# Power.net
KiCad netlist of a schematic drawn in Altium Designer
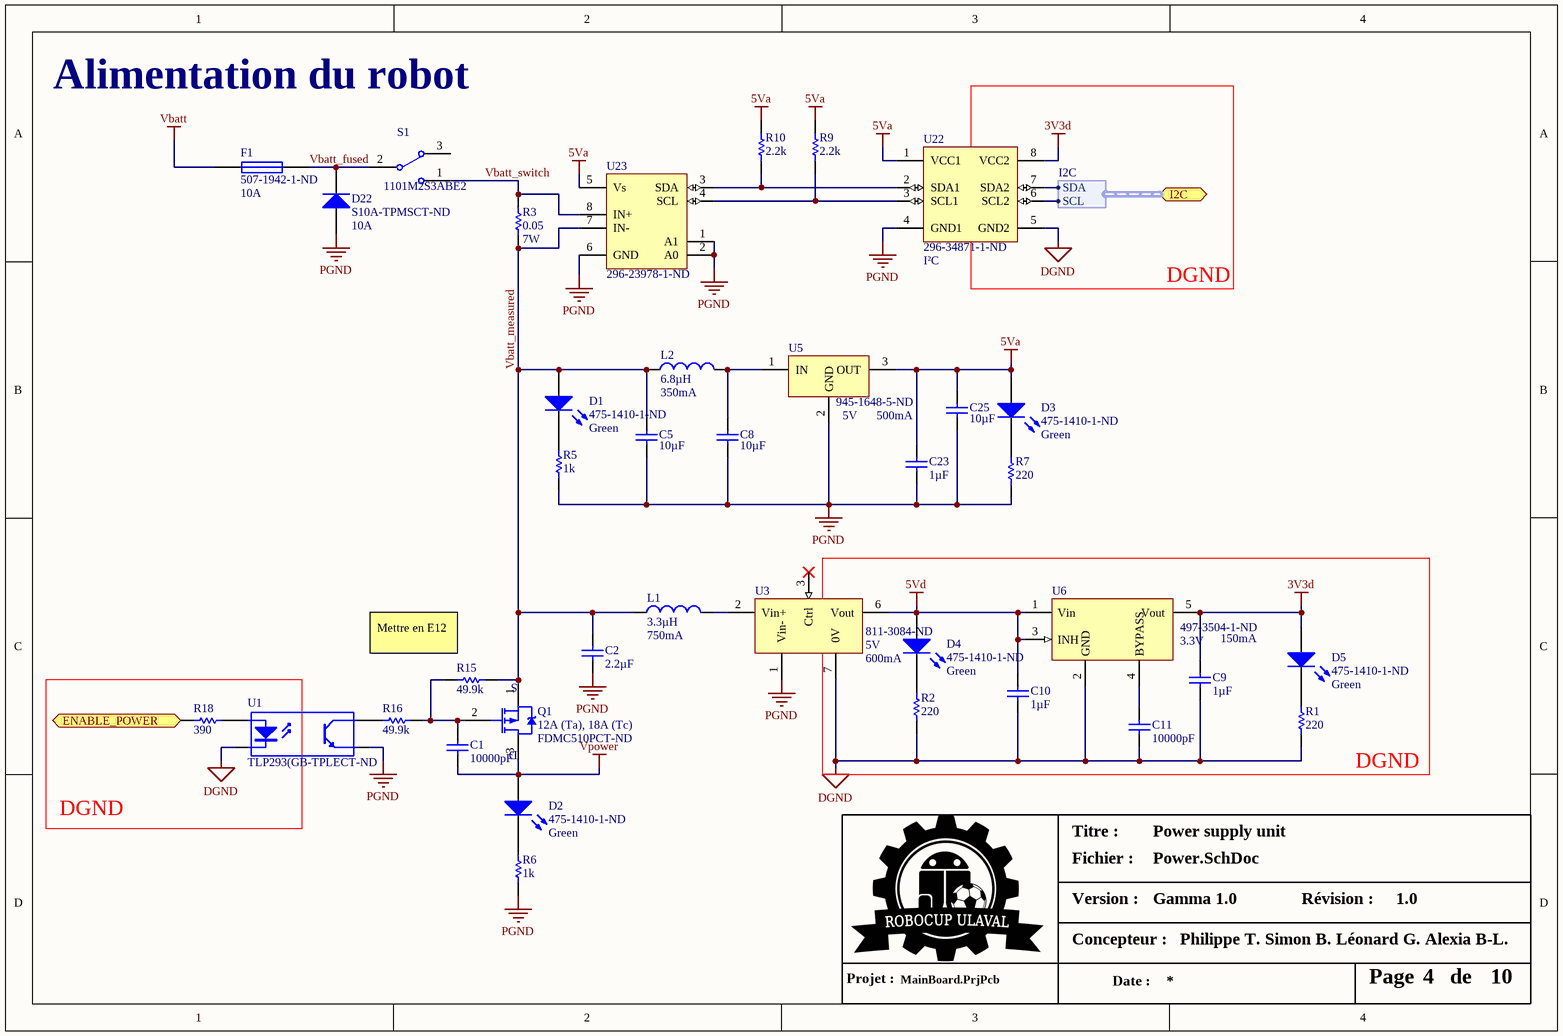
[diagram p0: Power.SchDoc]

(export (version "E")
  (design (tool "Eeschema 10.0.6"))
  (components
    (comp (ref "C1")
      (value "GRM188R71H103KA01D")
      (footprint "0603")
      (description "CAP CER 10000PF 50V X7R 0603")
      (fields
        (field (name "MANUFACTURER") "Murata Electronics North America")
        (field (name "TOLERANCE") "±10%")
        (field (name "CAPACITANCE") "10000pF")
      )
      (libsource (lib "ResCap") (part "GRM188R71H103KA01D"))
    )
    (comp (ref "C2")
      (value "CL21B225KAFNNWE")
      (footprint "0805")
      (description "CAP CER 2.2UF 25V X7R 0805")
      (fields
        (field (name "MANUFACTURER") "Samsung Electro-Mechanics America, Inc.")
        (field (name "TOLERANCE") "±10%")
        (field (name "CAPACITANCE") "2.2µF")
      )
      (libsource (lib "ResCap") (part "CL21B225KAFNNWE"))
    )
    (comp (ref "C5")
      (value "GMK316AB7106KL-TR")
      (footprint "1206")
      (description "CAP CER 10UF 35V X7R 1206")
      (fields
        (field (name "MANUFACTURER") "Taiyo Yuden")
        (field (name "CAPACITANCE") "10µF")
        (field (name "TOLERANCE") "±10%")
      )
      (libsource (lib "ResCap") (part "GMK316AB7106KL-TR"))
    )
    (comp (ref "C8")
      (value "GMK316AB7106KL-TR")
      (footprint "1206")
      (description "CAP CER 10UF 35V X7R 1206")
      (fields
        (field (name "MANUFACTURER") "Taiyo Yuden")
        (field (name "CAPACITANCE") "10µF")
        (field (name "TOLERANCE") "±10%")
      )
      (libsource (lib "ResCap") (part "GMK316AB7106KL-TR"))
    )
    (comp (ref "C9")
      (value "CL21B105KBFNFNE")
      (footprint "0805")
      (description "CAP CER 1UF 50V X7R 0805")
      (fields
        (field (name "MANUFACTURER") "Samsung Electro-Mechanics America, Inc.")
        (field (name "TOLERANCE") "±10%")
        (field (name "CAPACITANCE") "1µF")
      )
      (libsource (lib "ResCap") (part "CL21B105KBFNFNE"))
    )
    (comp (ref "C10")
      (value "CL21B105KBFNFNE")
      (footprint "0805")
      (description "CAP CER 1UF 50V X7R 0805")
      (fields
        (field (name "MANUFACTURER") "Samsung Electro-Mechanics America, Inc.")
        (field (name "TOLERANCE") "±10%")
        (field (name "CAPACITANCE") "1µF")
      )
      (libsource (lib "ResCap") (part "CL21B105KBFNFNE"))
    )
    (comp (ref "C11")
      (value "GRM188R71H103KA01D")
      (footprint "0603")
      (description "CAP CER 10000PF 50V X7R 0603")
      (fields
        (field (name "MANUFACTURER") "Murata Electronics North America")
        (field (name "TOLERANCE") "±10%")
        (field (name "CAPACITANCE") "10000pF")
      )
      (libsource (lib "ResCap") (part "GRM188R71H103KA01D"))
    )
    (comp (ref "C23")
      (value "CL21B105KBFNFNE")
      (footprint "0805")
      (description "CAP CER 1UF 50V X7R 0805")
      (fields
        (field (name "MANUFACTURER") "Samsung Electro-Mechanics America, Inc.")
        (field (name "TOLERANCE") "±10%")
        (field (name "CAPACITANCE") "1µF")
      )
      (libsource (lib "ResCap") (part "CL21B105KBFNFNE"))
    )
    (comp (ref "C25")
      (value "GMK316AB7106KL-TR")
      (footprint "1206")
      (description "CAP CER 10UF 35V X7R 1206")
      (fields
        (field (name "MANUFACTURER") "Taiyo Yuden")
        (field (name "CAPACITANCE") "10µF")
        (field (name "TOLERANCE") "±10%")
      )
      (libsource (lib "ResCap") (part "GMK316AB7106KL-TR"))
    )
    (comp (ref "D1")
      (value "LG R971-KN-1")
      (footprint "0805")
      (description "LED GREEN DIFFUSED 0805 SMD")
      (fields
        (field (name "MANUFACTURER") "OSRAM Opto Semiconductors Inc.")
        (field (name "SUPPLIER PART NUMBER 1") "475-1410-1-ND")
        (field (name "COLOR") "Green")
      )
      (libsource (lib "MainBoard") (part "LG R971-KN-1"))
    )
    (comp (ref "D2")
      (value "LG R971-KN-1")
      (footprint "0805")
      (description "LED GREEN DIFFUSED 0805 SMD")
      (fields
        (field (name "MANUFACTURER") "OSRAM Opto Semiconductors Inc.")
        (field (name "SUPPLIER PART NUMBER 1") "475-1410-1-ND")
        (field (name "COLOR") "Green")
      )
      (libsource (lib "MainBoard") (part "LG R971-KN-1"))
    )
    (comp (ref "D3")
      (value "LG R971-KN-1")
      (footprint "0805")
      (description "LED GREEN DIFFUSED 0805 SMD")
      (fields
        (field (name "MANUFACTURER") "OSRAM Opto Semiconductors Inc.")
        (field (name "SUPPLIER PART NUMBER 1") "475-1410-1-ND")
        (field (name "COLOR") "Green")
      )
      (libsource (lib "MainBoard") (part "LG R971-KN-1"))
    )
    (comp (ref "D4")
      (value "LG R971-KN-1")
      (footprint "0805")
      (description "LED GREEN DIFFUSED 0805 SMD")
      (fields
        (field (name "MANUFACTURER") "OSRAM Opto Semiconductors Inc.")
        (field (name "SUPPLIER PART NUMBER 1") "475-1410-1-ND")
        (field (name "COLOR") "Green")
      )
      (libsource (lib "MainBoard") (part "LG R971-KN-1"))
    )
    (comp (ref "D5")
      (value "LG R971-KN-1")
      (footprint "0805")
      (description "LED GREEN DIFFUSED 0805 SMD")
      (fields
        (field (name "MANUFACTURER") "OSRAM Opto Semiconductors Inc.")
        (field (name "SUPPLIER PART NUMBER 1") "475-1410-1-ND")
        (field (name "COLOR") "Green")
      )
      (libsource (lib "MainBoard") (part "LG R971-KN-1"))
    )
    (comp (ref "D22")
      (value "S10A-TP")
      (footprint "SMC")
      (description "DIODE GEN PURP 50V 10A DO214AB")
      (fields
        (field (name "MANUFACTURER") "Micro Commercial Co")
        (field (name "SUPPLIER PART NUMBER 1") "S10A-TPMSCT-ND")
        (field (name "CURRENT - AVERAGE RECTIFIED (IO)") "10A")
      )
      (libsource (lib "MainBoard") (part "S10A-TP"))
    )
    (comp (ref "F1")
      (value "C1H 10")
      (footprint "1206")
      (description "FUSE BOARD MNT 10A 125VAC 32VDC")
      (fields
        (field (name "MANUFACTURER") "Bel Fuse Inc.")
        (field (name "SUPPLIER PART NUMBER 1") "507-1942-1-ND")
        (field (name "CURRENT RATING") "10A")
      )
      (libsource (lib "MainBoard") (part "C1H 10"))
    )
    (comp (ref "L1")
      (value "MLZ2012N3R3LT000")
      (footprint "0805")
      (description "FIXED IND 3.3UH 750MA 150 MOHM")
      (fields
        (field (name "MANUFACTURER") "TDK Corporation")
        (field (name "TOLERANCE") "±20%")
        (field (name "INDUCTANCE") "3.3µH")
        (field (name "CURRENT RATING") "750mA")
      )
      (libsource (lib "MainBoard") (part "MLZ2012N3R3LT000"))
    )
    (comp (ref "L2")
      (value "MLZ2012M6R8WT000")
      (footprint "0805")
      (description "FIXED IND 6.8UH 350MA 400 MOHM")
      (fields
        (field (name "MANUFACTURER") "TDK Corporation")
        (field (name "TOLERANCE") "±20%")
        (field (name "INDUCTANCE") "6.8µH")
        (field (name "CURRENT RATING") "350mA")
      )
      (libsource (lib "MainBoard") (part "MLZ2012M6R8WT000"))
    )
    (comp (ref "Q1")
      (value "FDMC510P")
      (footprint "PowerPAK 1212-8")
      (description "MOSFET P-CH 20V 18A 8-MLP")
      (fields
        (field (name "MANUFACTURER") "Fairchild Semiconductor")
        (field (name "CURRENT - CONTINUOUS DRAIN (ID) @ 25°C") "12A (Ta), 18A (Tc)")
        (field (name "SUPPLIER PART NUMBER 1") "FDMC510PCT-ND")
      )
      (libsource (lib "MainBoard") (part "FDMC510P"))
    )
    (comp (ref "R1")
      (value "RC1206JR-07220RL")
      (footprint "1206")
      (description "RES SMD 220 OHM 5% 1/4W 1206")
      (fields
        (field (name "MANUFACTURER") "Yageo")
        (field (name "TOLERANCE") "±5%")
        (field (name "RESISTANCE (OHMS)") "220")
      )
      (libsource (lib "ResCap") (part "RC1206JR-07220RL"))
    )
    (comp (ref "R2")
      (value "RC1206JR-07220RL")
      (footprint "1206")
      (description "RES SMD 220 OHM 5% 1/4W 1206")
      (fields
        (field (name "MANUFACTURER") "Yageo")
        (field (name "TOLERANCE") "±5%")
        (field (name "RESISTANCE (OHMS)") "220")
      )
      (libsource (lib "ResCap") (part "RC1206JR-07220RL"))
    )
    (comp (ref "R3")
      (value "WSHM2818R0500FEA")
      (footprint "RESC7146X15N")
      (description "RES SMD 0.05 OHM 1% 7W 2818")
      (fields
        (field (name "MANUFACTURER") "Vishay Dale")
        (field (name "TOLERANCE") "±1%")
        (field (name "RESISTANCE (OHMS)") "0.05")
        (field (name "POWER (WATTS)") "7W")
      )
      (libsource (lib "ResCap") (part "WSHM2818R0500FEA"))
    )
    (comp (ref "R5")
      (value "RNCP1206FTD1K00")
      (footprint "1206")
      (description "RES SMD 1K OHM 1% 1/2W 1206")
      (fields
        (field (name "MANUFACTURER") "Stackpole Electronics Inc.")
        (field (name "TOLERANCE") "±1%")
        (field (name "RESISTANCE (OHMS)") "1k")
      )
      (libsource (lib "ResCap") (part "RNCP1206FTD1K00"))
    )
    (comp (ref "R6")
      (value "RC0603FR-072K2L")
      (footprint "1206")
      (description "RES SMD 1K OHM 1% 1/2W 1206")
      (fields
        (field (name "MANUFACTURER") "Stackpole Electronics Inc.")
        (field (name "MANUFACTURER PART NUMBER") "RNCP1206FTD1K00")
        (field (name "RESISTANCE (OHMS)") "1k")
      )
      (libsource (lib "ResCap") (part "RNCP1206FTD1K00"))
    )
    (comp (ref "R7")
      (value "RC1206JR-07220RL")
      (footprint "1206")
      (description "RES SMD 220 OHM 5% 1/4W 1206")
      (fields
        (field (name "MANUFACTURER") "Yageo")
        (field (name "TOLERANCE") "±5%")
        (field (name "RESISTANCE (OHMS)") "220")
      )
      (libsource (lib "ResCap") (part "RC1206JR-07220RL"))
    )
    (comp (ref "R9")
      (value "RC0603FR-072K2L")
      (footprint "0603")
      (description "RES SMD 2.2K OHM 1% 1/10W 0603")
      (fields
        (field (name "MANUFACTURER") "Yageo")
        (field (name "TOLERANCE") "±1%")
        (field (name "RESISTANCE (OHMS)") "2.2k")
      )
      (libsource (lib "ResCap") (part "RC0603FR-072K2L"))
    )
    (comp (ref "R10")
      (value "RC0603FR-072K2L")
      (footprint "0603")
      (description "RES SMD 2.2K OHM 1% 1/10W 0603")
      (fields
        (field (name "MANUFACTURER") "Yageo")
        (field (name "TOLERANCE") "±1%")
        (field (name "RESISTANCE (OHMS)") "2.2k")
      )
      (libsource (lib "ResCap") (part "RC0603FR-072K2L"))
    )
    (comp (ref "R15")
      (value "RC0603FR-0749K9L")
      (footprint "0603")
      (description "RES SMD 49.9K OHM 1% 1/10W 0603")
      (fields
        (field (name "MANUFACTURER") "Yageo")
        (field (name "TOLERANCE") "±1%")
        (field (name "RESISTANCE (OHMS)") "49.9k")
      )
      (libsource (lib "ResCap") (part "RC0603FR-0749K9L"))
    )
    (comp (ref "R16")
      (value "RC0603FR-0749K9L")
      (footprint "0603")
      (description "RES SMD 49.9K OHM 1% 1/10W 0603")
      (fields
        (field (name "MANUFACTURER") "Yageo")
        (field (name "TOLERANCE") "±1%")
        (field (name "RESISTANCE (OHMS)") "49.9k")
      )
      (libsource (lib "ResCap") (part "RC0603FR-0749K9L"))
    )
    (comp (ref "R18")
      (value "RC0603JR-07390RL")
      (footprint "0603")
      (description "RES SMD 390 OHM 5% 1/10W 0603")
      (fields
        (field (name "MANUFACTURER") "Yageo")
        (field (name "TOLERANCE") "±5%")
        (field (name "RESISTANCE (OHMS)") "390")
      )
      (libsource (lib "ResCap") (part "RC0603JR-07390RL"))
    )
    (comp (ref "S1")
      (value "1101M2S3ABE2")
      (footprint "C&K Switch")
      (description "SWITCH SLIDE SPDT 0.4VA 20V")
      (fields (field (name "MANUFACTURER") "C&K Components"))
      (libsource (lib "MainBoard") (part "1101M2S3ABE2"))
    )
    (comp (ref "U1")
      (value "TLP293(GB-TPL,E")
      (footprint "SOIC127P700X220-4N")
      (description "OPTOISOLATOR 3.75KV TRANS 4-SO")
      (fields
        (field (name "MANUFACTURER") "Toshiba Semiconductor and Storage")
        (field (name "SUPPLIER PART NUMBER 1") "TLP293(GB-TPLECT-ND")
      )
      (libsource (lib "MainBoard") (part "TLP293(GB-TPL,E"))
    )
    (comp (ref "U3")
      (value "NCS3S1205SC")
      (footprint "NCS3S")
      (description "DC/DC CONVERTER 5V 3W")
      (fields
        (field (name "MANUFACTURER") "Murata Power Solutions Inc.")
        (field (name "SUPPLIER PART NUMBER 1") "811-3084-ND")
        (field (name "VOLTAGE - OUTPUT 1") "5V")
        (field (name "CURRENT - OUTPUT (MAX)") "600mA")
      )
      (libsource (lib "MainBoard") (part "NCS3S1205SC"))
    )
    (comp (ref "U5")
      (value "R-78E5.0-0.5")
      (footprint "3-SIP MOdule")
      (description "CONV DC/DC 5V 500MA OUT THRU")
      (fields
        (field (name "MANUFACTURER") "Recom Power")
        (field (name "SUPPLIER PART NUMBER 1") "945-1648-5-ND")
        (field (name "VOLTAGE - OUTPUT 1") "5V")
        (field (name "CURRENT - OUTPUT (MAX)") "500mA")
      )
      (libsource (lib "MainBoard") (part "R-78E5.0-0.5"))
    )
    (comp (ref "U6")
      (value "LD3985M33R")
      (footprint "SOT-23-5")
      (description "IC REG LDO 3.3V 0.15A SOT23-5")
      (fields
        (field (name "MANUFACTURER") "STMicroelectronics")
        (field (name "SUPPLIER PART NUMBER 1") "497-3504-1-ND")
        (field (name "VOLTAGE - OUTPUT") "3.3V")
        (field (name "CURRENT - OUTPUT") "150mA")
      )
      (libsource (lib "MainBoard") (part "LD3985M33R"))
    )
    (comp (ref "U22")
      (value "ISO1540DR")
      (footprint "SOIC127P600X175-8N")
      (description "DGTL ISO 2.5KV 2CH I2C 8SOIC")
      (fields
        (field (name "MANUFACTURER") "Texas Instruments")
        (field (name "SUPPLIER PART NUMBER 1") "296-34871-1-ND")
        (field (name "TYPE") "I²C")
      )
      (libsource (lib "MainBoard") (part "ISO1540DR"))
    )
    (comp (ref "U23")
      (value "INA219AIDR")
      (footprint "SOIC127P600X175-8N")
      (description "IC CURRENT MONITOR 1% 8SOIC")
      (fields
        (field (name "MANUFACTURER") "Texas Instruments")
        (field (name "SUPPLIER PART NUMBER 1") "296-23978-1-ND")
      )
      (libsource (lib "MainBoard") (part "INA219AIDR"))
    )
  )
  (nets
    (net (code "2") (name "/ENABLE_POWER") (class "Default")
      (node (ref "R18") (pin "1") (pinfunction "1_1") (pintype "passive"))
    )
    (net (code "3") (name "/SCL") (class "Default")
      (node (ref "U22") (pin "6") (pinfunction "SCL2_6") (pintype "bidirectional"))
    )
    (net (code "4") (name "/SDA") (class "Default")
      (node (ref "U22") (pin "7") (pinfunction "SDA2_7") (pintype "bidirectional"))
    )
    (net (code "5") (name "/Vbatt_fused") (class "Default")
      (node (ref "D22") (pin "2") (pinfunction "K_2") (pintype "passive"))
      (node (ref "F1") (pin "2") (pinfunction "2_2") (pintype "passive"))
      (node (ref "S1") (pin "2") (pinfunction "2_2") (pintype "passive"))
    )
    (net (code "6") (name "/Vbatt_measured") (class "Default")
      (node (ref "C2") (pin "2") (pinfunction "2_2") (pintype "passive"))
      (node (ref "C5") (pin "2") (pinfunction "2_2") (pintype "passive"))
      (node (ref "D1") (pin "1") (pinfunction "A_1") (pintype "passive"))
      (node (ref "L1") (pin "1") (pinfunction "1_1") (pintype "passive"))
      (node (ref "L2") (pin "1") (pinfunction "1_1") (pintype "passive"))
      (node (ref "Q1") (pin "1") (pinfunction "S_1") (pintype "passive"))
      (node (ref "R15") (pin "2") (pinfunction "2_2") (pintype "passive"))
      (node (ref "R3") (pin "1") (pinfunction "1_1") (pintype "passive"))
      (node (ref "U23") (pin "7") (pinfunction "IN-_7") (pintype "power_in"))
    )
    (net (code "7") (name "/Vbatt_switch") (class "Default")
      (node (ref "R3") (pin "2") (pinfunction "2_2") (pintype "passive"))
      (node (ref "S1") (pin "1") (pinfunction "1_1") (pintype "passive"))
      (node (ref "U23") (pin "8") (pinfunction "IN+_8") (pintype "power_in"))
    )
    (net (code "9") (name "3V3d") (class "Default")
      (node (ref "C9") (pin "2") (pinfunction "2_2") (pintype "passive"))
      (node (ref "D5") (pin "1") (pinfunction "A_1") (pintype "passive"))
      (node (ref "U22") (pin "8") (pinfunction "VCC2_8") (pintype "power_in"))
      (node (ref "U6") (pin "5") (pinfunction "Vout_5") (pintype "power_in"))
    )
    (net (code "10") (name "5Va") (class "Default")
      (node (ref "C23") (pin "2") (pinfunction "2_2") (pintype "passive"))
      (node (ref "C25") (pin "2") (pinfunction "2_2") (pintype "passive"))
      (node (ref "D3") (pin "1") (pinfunction "A_1") (pintype "passive"))
      (node (ref "R10") (pin "2") (pinfunction "2_2") (pintype "passive"))
      (node (ref "R9") (pin "2") (pinfunction "2_2") (pintype "passive"))
      (node (ref "U22") (pin "1") (pinfunction "VCC1_1") (pintype "power_in"))
      (node (ref "U23") (pin "5") (pinfunction "Vs_5") (pintype "power_in"))
      (node (ref "U5") (pin "3") (pinfunction "OUT_3") (pintype "power_in"))
    )
    (net (code "11") (name "5Vd") (class "Default")
      (node (ref "C10") (pin "2") (pinfunction "2_2") (pintype "passive"))
      (node (ref "D4") (pin "1") (pinfunction "A_1") (pintype "passive"))
      (node (ref "U3") (pin "6") (pinfunction "Vout_6") (pintype "power_in"))
      (node (ref "U6") (pin "1") (pinfunction "Vin_1") (pintype "power_in"))
      (node (ref "U6") (pin "3") (pinfunction "INH_3") (pintype "input"))
    )
    (net (code "12") (name "DGND") (class "Default")
      (node (ref "C10") (pin "1") (pinfunction "1_1") (pintype "passive"))
      (node (ref "C11") (pin "1") (pinfunction "1_1") (pintype "passive"))
      (node (ref "C9") (pin "1") (pinfunction "1_1") (pintype "passive"))
      (node (ref "R1") (pin "1") (pinfunction "1_1") (pintype "passive"))
      (node (ref "R2") (pin "1") (pinfunction "1_1") (pintype "passive"))
      (node (ref "U1") (pin "2") (pinfunction "K_2") (pintype "passive"))
      (node (ref "U22") (pin "5") (pinfunction "GND2_5") (pintype "power_in"))
      (node (ref "U3") (pin "7") (pinfunction "0V_7") (pintype "power_in"))
      (node (ref "U6") (pin "2") (pinfunction "GND_2") (pintype "power_in"))
    )
    (net (code "13") (name "Net-(D1-K)") (class "Default")
      (node (ref "D1") (pin "2") (pinfunction "K_2") (pintype "passive"))
      (node (ref "R5") (pin "2") (pinfunction "2_2") (pintype "passive"))
    )
    (net (code "14") (name "Net-(D2-K)") (class "Default")
      (node (ref "D2") (pin "2") (pinfunction "K_2") (pintype "passive"))
      (node (ref "R6") (pin "2") (pinfunction "2_2") (pintype "passive"))
    )
    (net (code "15") (name "Net-(D3-K)") (class "Default")
      (node (ref "D3") (pin "2") (pinfunction "K_2") (pintype "passive"))
      (node (ref "R7") (pin "2") (pinfunction "2_2") (pintype "passive"))
    )
    (net (code "16") (name "Net-(D4-K)") (class "Default")
      (node (ref "D4") (pin "2") (pinfunction "K_2") (pintype "passive"))
      (node (ref "R2") (pin "2") (pinfunction "2_2") (pintype "passive"))
    )
    (net (code "17") (name "Net-(D5-K)") (class "Default")
      (node (ref "D5") (pin "2") (pinfunction "K_2") (pintype "passive"))
      (node (ref "R1") (pin "2") (pinfunction "2_2") (pintype "passive"))
    )
    (net (code "18") (name "Net-(Q1-G)") (class "Default")
      (node (ref "C1") (pin "2") (pinfunction "2_2") (pintype "passive"))
      (node (ref "Q1") (pin "2") (pinfunction "G_2") (pintype "passive"))
      (node (ref "R15") (pin "1") (pinfunction "1_1") (pintype "passive"))
      (node (ref "R16") (pin "2") (pinfunction "2_2") (pintype "passive"))
    )
    (net (code "19") (name "Net-(U1-A)") (class "Default")
      (node (ref "R18") (pin "2") (pinfunction "2_2") (pintype "passive"))
      (node (ref "U1") (pin "1") (pinfunction "A_1") (pintype "passive"))
    )
    (net (code "20") (name "Net-(U1-C)") (class "Default")
      (node (ref "R16") (pin "1") (pinfunction "1_1") (pintype "passive"))
      (node (ref "U1") (pin "4") (pinfunction "C_4") (pintype "passive"))
    )
    (net (code "21") (name "Net-(U3-Vin+)") (class "Default")
      (node (ref "L1") (pin "2") (pinfunction "2_2") (pintype "passive"))
      (node (ref "U3") (pin "2") (pinfunction "Vin+_2") (pintype "power_in"))
    )
    (net (code "22") (name "Net-(U5-IN)") (class "Default")
      (node (ref "C8") (pin "2") (pinfunction "2_2") (pintype "passive"))
      (node (ref "L2") (pin "2") (pinfunction "2_2") (pintype "passive"))
      (node (ref "U5") (pin "1") (pinfunction "IN_1") (pintype "power_in"))
    )
    (net (code "23") (name "Net-(U6-BYPASS)") (class "Default")
      (node (ref "C11") (pin "2") (pinfunction "2_2") (pintype "passive"))
      (node (ref "U6") (pin "4") (pinfunction "BYPASS_4") (pintype "passive"))
    )
    (net (code "24") (name "Net-(U22-SCL1)") (class "Default")
      (node (ref "R9") (pin "1") (pinfunction "1_1") (pintype "passive"))
      (node (ref "U22") (pin "3") (pinfunction "SCL1_3") (pintype "bidirectional"))
      (node (ref "U23") (pin "4") (pinfunction "SCL_4") (pintype "bidirectional"))
    )
    (net (code "25") (name "Net-(U22-SDA1)") (class "Default")
      (node (ref "R10") (pin "1") (pinfunction "1_1") (pintype "passive"))
      (node (ref "U22") (pin "2") (pinfunction "SDA1_2") (pintype "bidirectional"))
      (node (ref "U23") (pin "3") (pinfunction "SDA_3") (pintype "bidirectional"))
    )
    (net (code "26") (name "PGND") (class "Default")
      (node (ref "C2") (pin "1") (pinfunction "1_1") (pintype "passive"))
      (node (ref "C23") (pin "1") (pinfunction "1_1") (pintype "passive"))
      (node (ref "C25") (pin "1") (pinfunction "1_1") (pintype "passive"))
      (node (ref "C5") (pin "1") (pinfunction "1_1") (pintype "passive"))
      (node (ref "C8") (pin "1") (pinfunction "1_1") (pintype "passive"))
      (node (ref "D22") (pin "1") (pinfunction "A_1") (pintype "passive"))
      (node (ref "R5") (pin "1") (pinfunction "1_1") (pintype "passive"))
      (node (ref "R6") (pin "1") (pinfunction "1_1") (pintype "passive"))
      (node (ref "R7") (pin "1") (pinfunction "1_1") (pintype "passive"))
      (node (ref "U1") (pin "3") (pinfunction "E_3") (pintype "passive"))
      (node (ref "U22") (pin "4") (pinfunction "GND1_4") (pintype "power_in"))
      (node (ref "U23") (pin "1") (pinfunction "A1_1") (pintype "passive"))
      (node (ref "U23") (pin "2") (pinfunction "A0_2") (pintype "passive"))
      (node (ref "U23") (pin "6") (pinfunction "GND_6") (pintype "power_in"))
      (node (ref "U3") (pin "1") (pinfunction "Vin-_1") (pintype "power_in"))
      (node (ref "U5") (pin "2") (pinfunction "GND_2") (pintype "power_in"))
    )
    (net (code "27") (name "Vbatt") (class "Default")
      (node (ref "F1") (pin "1") (pinfunction "1_1") (pintype "passive"))
    )
    (net (code "28") (name "Vpower") (class "Default")
      (node (ref "C1") (pin "1") (pinfunction "1_1") (pintype "passive"))
      (node (ref "D2") (pin "1") (pinfunction "A_1") (pintype "passive"))
      (node (ref "Q1") (pin "3") (pinfunction "D_3") (pintype "passive"))
    )
    (net (code "29") (name "unconnected-(S1-Pad3)") (class "Default")
      (node (ref "S1") (pin "3") (pinfunction "3_3") (pintype "passive"))
    )
    (net (code "30") (name "unconnected-(U3-Ctrl-Pad3)") (class "Default")
      (node (ref "U3") (pin "3") (pinfunction "Ctrl_3") (pintype "input+no_connect"))
    )
  )
)
